# PinscapePico_KL25Z_Adapter_-_PCA9555_vsn.net
KiCad netlist of a schematic drawn in EAGLE
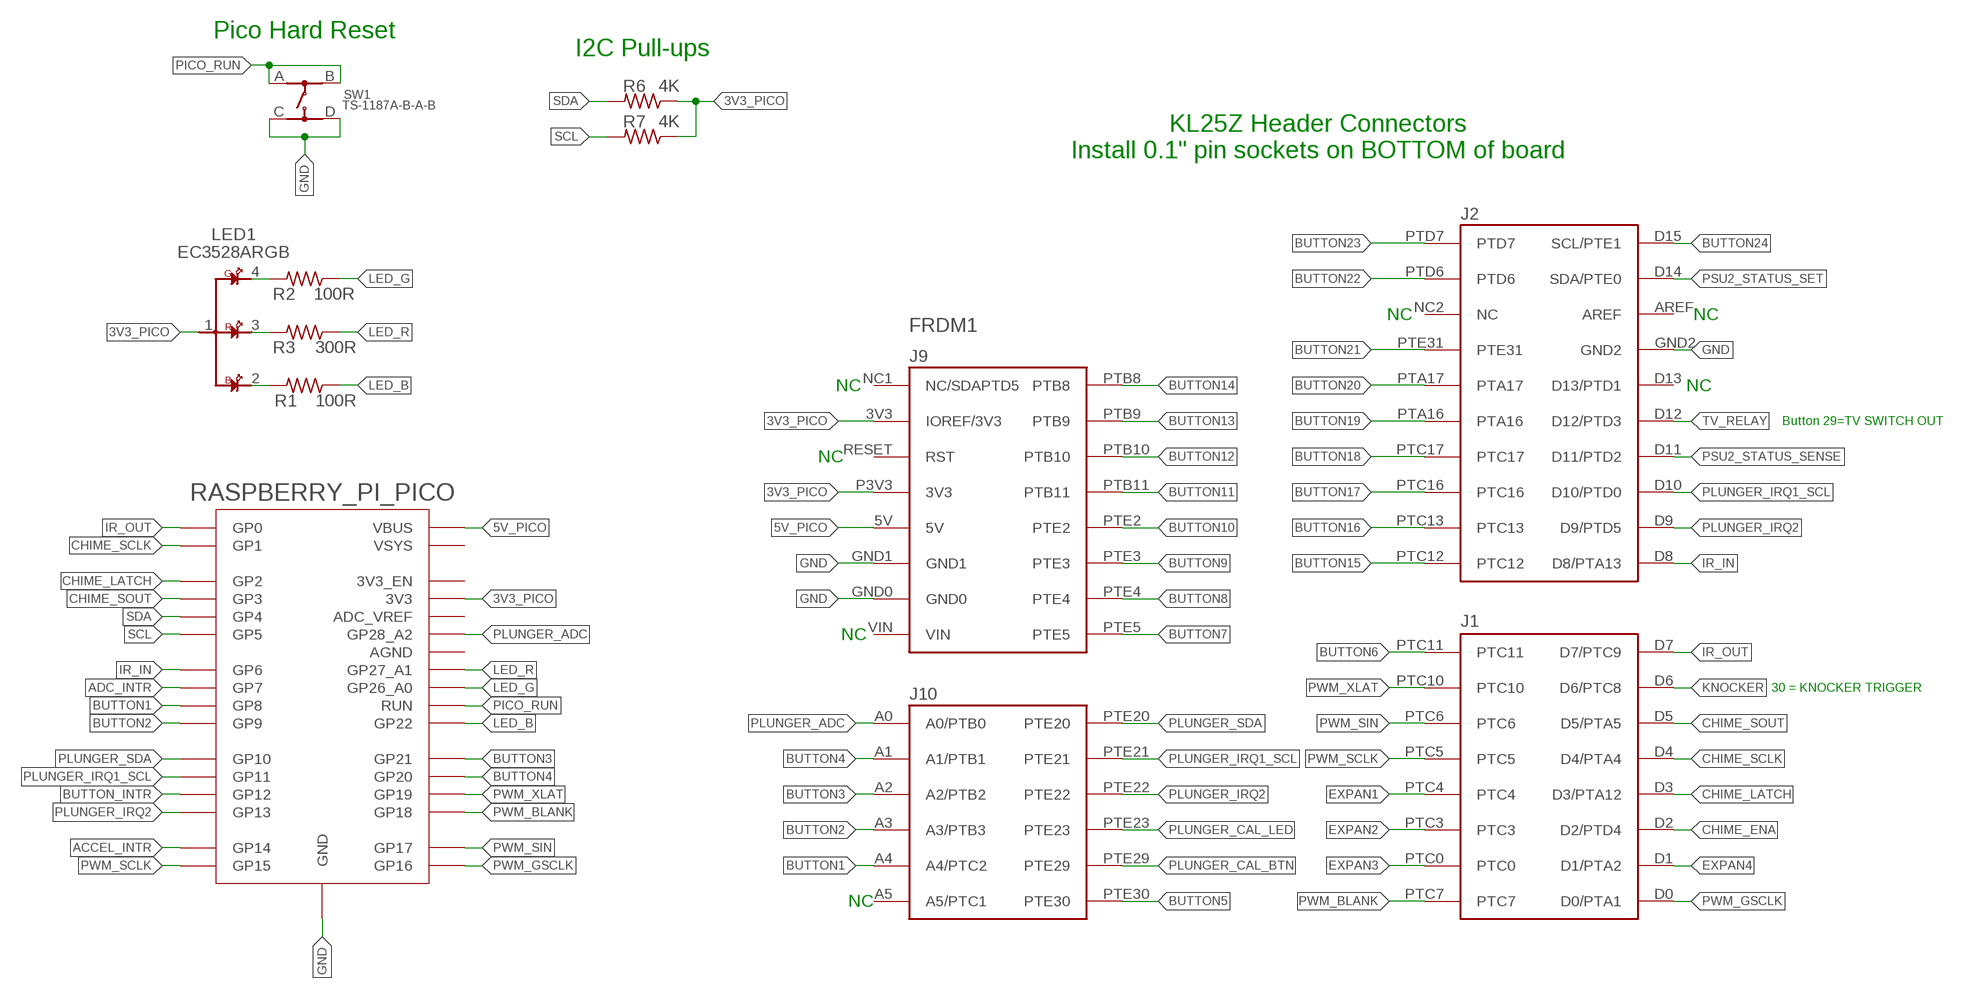
[diagram p0: schematic, sheet 1]
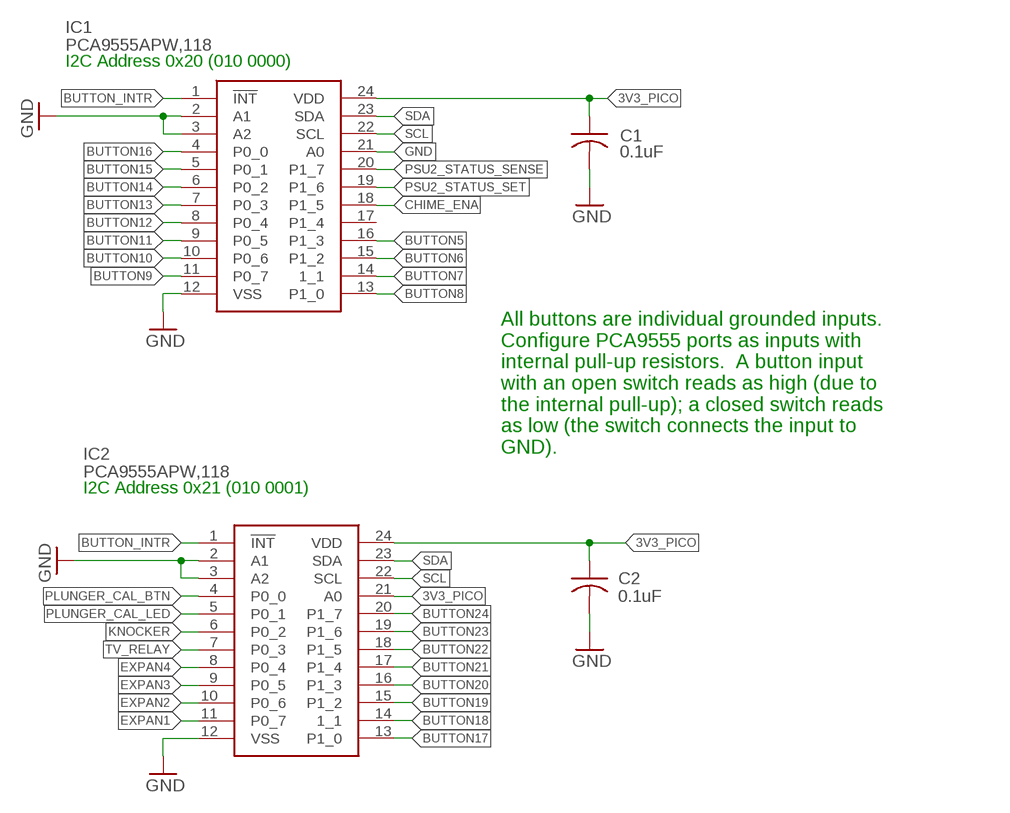
[diagram p1: schematic, sheet 2]
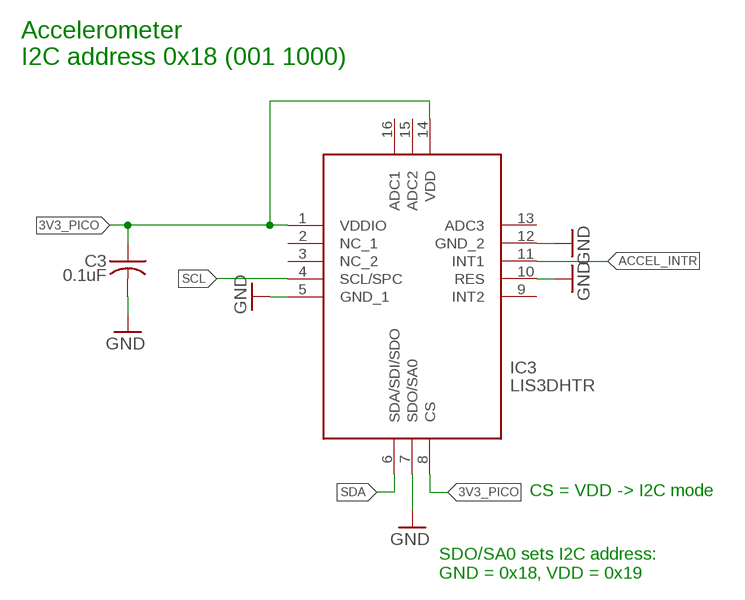
[diagram p2: schematic, sheet 3]
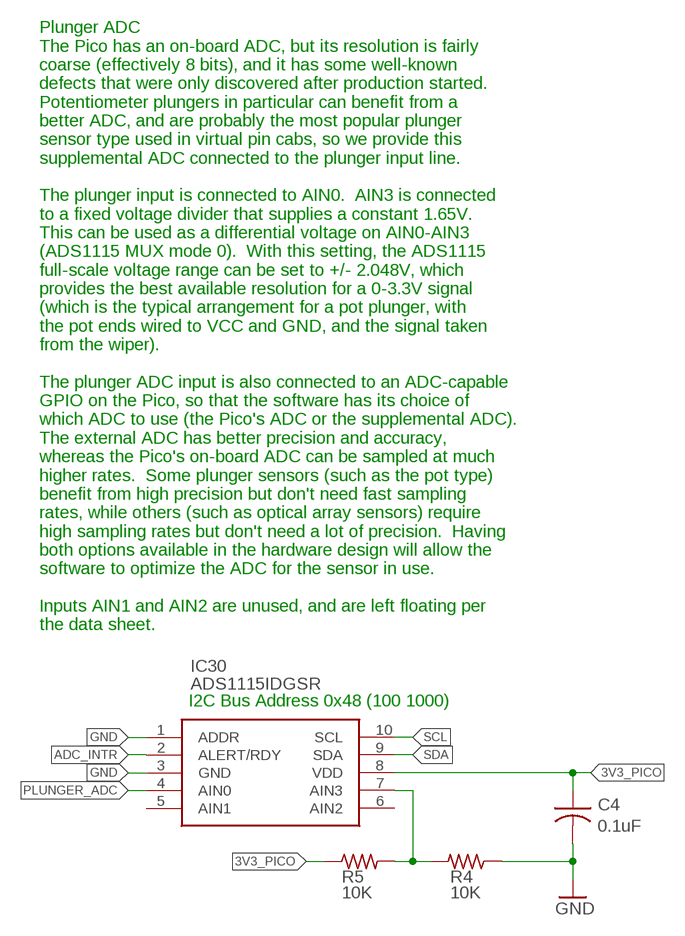
[diagram p3: schematic, sheet 4]

(export (version "E")
  (design (tool "Eeschema 10.0.6"))
  (components
    (comp (ref "C4")
      (value "0.1uF")
      (footprint "eagle-import:C1206")
      (libsource (lib "eagle-import") (part "C-USC1206"))
    )
    (comp (ref "IC30")
      (value "ADS1115IDGSR")
      (footprint "eagle-import:SOP50P490X110-10N")
      (fields (field (name "MOUSER_PART_NUMBER") "595-ADS1115IDGSR"))
      (libsource (lib "eagle-import") (part "ADS1115IDGSR"))
    )
    (comp (ref "R4")
      (value "10K")
      (footprint "eagle-import:R1206")
      (libsource (lib "eagle-import") (part "R-US_R1206"))
    )
    (comp (ref "R5")
      (value "10K")
      (footprint "eagle-import:R1206")
      (libsource (lib "eagle-import") (part "R-US_R1206"))
    )
    (comp (ref "C1")
      (value "0.1uF")
      (footprint "eagle-import:C1206")
      (libsource (lib "eagle-import") (part "C-USC1206"))
    )
    (comp (ref "C2")
      (value "0.1uF")
      (footprint "eagle-import:C1206")
      (libsource (lib "eagle-import") (part "C-USC1206"))
    )
    (comp (ref "IC1")
      (value "PCA9555APW,118")
      (footprint "eagle-import:SOP65P640X110-24N")
      (fields (field (name "MOUSER_PART_NUMBER") "771-PCA9555APW118"))
      (libsource (lib "eagle-import") (part "PCA9555APW,118"))
    )
    (comp (ref "IC2")
      (value "PCA9555APW,118")
      (footprint "eagle-import:SOP65P640X110-24N")
      (fields (field (name "MOUSER_PART_NUMBER") "771-PCA9555APW118"))
      (libsource (lib "eagle-import") (part "PCA9555APW,118"))
    )
    (comp (ref "FRDM1")
      (value "KL25Z")
      (footprint "eagle-import:FRDM_KL25Z_NORMAL")
      (libsource (lib "eagle-import") (part "FRDM-KL25ZNORMAL"))
    )
    (comp (ref "LED1")
      (value "EC3528ARGB")
      (footprint "eagle-import:EC3528ARGB")
      (libsource (lib "eagle-import") (part "EC3528ARGB"))
    )
    (comp (ref "R1")
      (value "100R")
      (footprint "eagle-import:R1206")
      (libsource (lib "eagle-import") (part "R-US_R1206"))
    )
    (comp (ref "R2")
      (value "100R")
      (footprint "eagle-import:R1206")
      (libsource (lib "eagle-import") (part "R-US_R1206"))
    )
    (comp (ref "R3")
      (value "300R")
      (footprint "eagle-import:R1206")
      (libsource (lib "eagle-import") (part "R-US_R1206"))
    )
    (comp (ref "R6")
      (value "4K")
      (footprint "eagle-import:R1206")
      (libsource (lib "eagle-import") (part "R-US_R1206"))
    )
    (comp (ref "R7")
      (value "4K")
      (footprint "eagle-import:R1206")
      (libsource (lib "eagle-import") (part "R-US_R1206"))
    )
    (comp (ref "RASPBERRY_PI_PICO")
      (value "RPI_PICO_NO_DEBUG")
      (footprint "eagle-import:RPI_PICO_TH_NO_DEBUG")
      (libsource (lib "eagle-import") (part "RPI_PICO_NO_DEBUG"))
    )
    (comp (ref "SW1")
      (value "TS-1187A-B-A-B")
      (footprint "eagle-import:TS-1187A-B-A-B")
      (libsource (lib "eagle-import") (part "TS-1187A-B-A-B"))
    )
    (comp (ref "C3")
      (value "0.1uF")
      (footprint "eagle-import:C1206")
      (libsource (lib "eagle-import") (part "C-USC1206"))
    )
    (comp (ref "IC3")
      (value "LIS3DHTR")
      (footprint "eagle-import:LIS3DHTR")
      (fields (field (name "MOUSER_PART_NUMBER") "511-LIS3DHTR"))
      (libsource (lib "eagle-import") (part "LIS3DHTR"))
    )
  )
  (nets
    (net (code "1") (name "3V3_PICO") (class "Default")
      (node (ref "C1") (pin "1") (pinfunction "1_1") (pintype "passive"))
      (node (ref "C2") (pin "1") (pinfunction "1_1") (pintype "passive"))
      (node (ref "C3") (pin "1") (pinfunction "1_1") (pintype "passive"))
      (node (ref "C4") (pin "1") (pinfunction "1_1") (pintype "passive"))
      (node (ref "FRDM1") (pin "3V3") (pinfunction "IOREF/3V3_3V3") (pintype "bidirectional"))
      (node (ref "FRDM1") (pin "P3V3") (pinfunction "3V3_P3V3") (pintype "bidirectional"))
      (node (ref "IC1") (pin "24") (pinfunction "VDD_24") (pintype "bidirectional"))
      (node (ref "IC2") (pin "21") (pinfunction "A0_21") (pintype "bidirectional"))
      (node (ref "IC2") (pin "24") (pinfunction "VDD_24") (pintype "bidirectional"))
      (node (ref "IC3") (pin "1") (pinfunction "VDDIO_1") (pintype "power_in"))
      (node (ref "IC3") (pin "14") (pinfunction "VDD_14") (pintype "power_in"))
      (node (ref "IC3") (pin "8") (pinfunction "CS_8") (pintype "input"))
      (node (ref "IC30") (pin "8") (pinfunction "VDD_8") (pintype "bidirectional"))
      (node (ref "LED1") (pin "1") (pinfunction "1_1") (pintype "bidirectional"))
      (node (ref "R5") (pin "1") (pinfunction "1_1") (pintype "passive"))
      (node (ref "R6") (pin "1") (pinfunction "1_1") (pintype "passive"))
      (node (ref "R7") (pin "1") (pinfunction "1_1") (pintype "passive"))
      (node (ref "RASPBERRY_PI_PICO") (pin "3V3") (pinfunction "3V3_3V3") (pintype "bidirectional"))
    )
    (net (code "2") (name "5V_PICO") (class "Default")
      (node (ref "FRDM1") (pin "5V") (pinfunction "5V_5V") (pintype "bidirectional"))
      (node (ref "RASPBERRY_PI_PICO") (pin "VBUS") (pinfunction "VBUS_VBUS") (pintype "bidirectional"))
    )
    (net (code "3") (name "ACCEL_INTR") (class "Default")
      (node (ref "IC3") (pin "11") (pinfunction "INT1_11") (pintype "input"))
      (node (ref "RASPBERRY_PI_PICO") (pin "GP14") (pinfunction "GP14_GP14") (pintype "bidirectional"))
    )
    (net (code "4") (name "ADC_INTR") (class "Default")
      (node (ref "IC30") (pin "2") (pinfunction "ALERT/RDY_2") (pintype "bidirectional"))
      (node (ref "RASPBERRY_PI_PICO") (pin "GP7") (pinfunction "GP7_GP7") (pintype "bidirectional"))
    )
    (net (code "5") (name "BUTTON1") (class "Default")
      (node (ref "FRDM1") (pin "A4") (pinfunction "A4/PTC2_A4") (pintype "bidirectional"))
      (node (ref "RASPBERRY_PI_PICO") (pin "GP8") (pinfunction "GP8_GP8") (pintype "bidirectional"))
    )
    (net (code "6") (name "BUTTON2") (class "Default")
      (node (ref "FRDM1") (pin "A3") (pinfunction "A3/PTB3_A3") (pintype "bidirectional"))
      (node (ref "RASPBERRY_PI_PICO") (pin "GP9") (pinfunction "GP9_GP9") (pintype "bidirectional"))
    )
    (net (code "7") (name "BUTTON3") (class "Default")
      (node (ref "FRDM1") (pin "A2") (pinfunction "A2/PTB2_A2") (pintype "bidirectional"))
      (node (ref "RASPBERRY_PI_PICO") (pin "GP21") (pinfunction "GP21_GP21") (pintype "bidirectional"))
    )
    (net (code "8") (name "BUTTON4") (class "Default")
      (node (ref "FRDM1") (pin "A1") (pinfunction "A1/PTB1_A1") (pintype "bidirectional"))
      (node (ref "RASPBERRY_PI_PICO") (pin "GP20") (pinfunction "GP20_GP20") (pintype "bidirectional"))
    )
    (net (code "9") (name "BUTTON5") (class "Default")
      (node (ref "FRDM1") (pin "PTE30") (pinfunction "PTE30_PTE30") (pintype "bidirectional"))
      (node (ref "IC1") (pin "16") (pinfunction "P1_3_16") (pintype "bidirectional"))
    )
    (net (code "10") (name "BUTTON6") (class "Default")
      (node (ref "FRDM1") (pin "PTC11") (pinfunction "PTC11_PTC11") (pintype "bidirectional"))
      (node (ref "IC1") (pin "15") (pinfunction "P1_2_15") (pintype "bidirectional"))
    )
    (net (code "11") (name "BUTTON7") (class "Default")
      (node (ref "FRDM1") (pin "PTE5") (pinfunction "PTE5_PTE5") (pintype "bidirectional"))
      (node (ref "IC1") (pin "14") (pinfunction "1_1_14") (pintype "bidirectional"))
    )
    (net (code "12") (name "BUTTON8") (class "Default")
      (node (ref "FRDM1") (pin "PTE4") (pinfunction "PTE4_PTE4") (pintype "bidirectional"))
      (node (ref "IC1") (pin "13") (pinfunction "P1_0_13") (pintype "bidirectional"))
    )
    (net (code "13") (name "BUTTON9") (class "Default")
      (node (ref "FRDM1") (pin "PTE3") (pinfunction "PTE3_PTE3") (pintype "bidirectional"))
      (node (ref "IC1") (pin "11") (pinfunction "P0_7_11") (pintype "bidirectional"))
    )
    (net (code "14") (name "BUTTON10") (class "Default")
      (node (ref "FRDM1") (pin "PTE2") (pinfunction "PTE2_PTE2") (pintype "bidirectional"))
      (node (ref "IC1") (pin "10") (pinfunction "P0_6_10") (pintype "bidirectional"))
    )
    (net (code "15") (name "BUTTON11") (class "Default")
      (node (ref "FRDM1") (pin "PTB11") (pinfunction "PTB11_PTB11") (pintype "bidirectional"))
      (node (ref "IC1") (pin "9") (pinfunction "P0_5_9") (pintype "bidirectional"))
    )
    (net (code "16") (name "BUTTON12") (class "Default")
      (node (ref "FRDM1") (pin "PTB10") (pinfunction "PTB10_PTB10") (pintype "bidirectional"))
      (node (ref "IC1") (pin "8") (pinfunction "P0_4_8") (pintype "bidirectional"))
    )
    (net (code "17") (name "BUTTON13") (class "Default")
      (node (ref "FRDM1") (pin "PTB9") (pinfunction "PTB9_PTB9") (pintype "bidirectional"))
      (node (ref "IC1") (pin "7") (pinfunction "P0_3_7") (pintype "bidirectional"))
    )
    (net (code "18") (name "BUTTON14") (class "Default")
      (node (ref "FRDM1") (pin "PTB8") (pinfunction "PTB8_PTB8") (pintype "bidirectional"))
      (node (ref "IC1") (pin "6") (pinfunction "P0_2_6") (pintype "bidirectional"))
    )
    (net (code "19") (name "BUTTON15") (class "Default")
      (node (ref "FRDM1") (pin "PTC12") (pinfunction "PTC12_PTC12") (pintype "bidirectional"))
      (node (ref "IC1") (pin "5") (pinfunction "P0_1_5") (pintype "bidirectional"))
    )
    (net (code "20") (name "BUTTON16") (class "Default")
      (node (ref "FRDM1") (pin "PTC13") (pinfunction "PTC13_PTC13") (pintype "bidirectional"))
      (node (ref "IC1") (pin "4") (pinfunction "P0_0_4") (pintype "bidirectional"))
    )
    (net (code "21") (name "BUTTON17") (class "Default")
      (node (ref "FRDM1") (pin "PTC16") (pinfunction "PTC16_PTC16") (pintype "bidirectional"))
      (node (ref "IC2") (pin "13") (pinfunction "P1_0_13") (pintype "bidirectional"))
    )
    (net (code "22") (name "BUTTON18") (class "Default")
      (node (ref "FRDM1") (pin "PTC17") (pinfunction "PTC17_PTC17") (pintype "bidirectional"))
      (node (ref "IC2") (pin "14") (pinfunction "1_1_14") (pintype "bidirectional"))
    )
    (net (code "23") (name "BUTTON19") (class "Default")
      (node (ref "FRDM1") (pin "PTA16") (pinfunction "PTA16_PTA16") (pintype "bidirectional"))
      (node (ref "IC2") (pin "15") (pinfunction "P1_2_15") (pintype "bidirectional"))
    )
    (net (code "24") (name "BUTTON20") (class "Default")
      (node (ref "FRDM1") (pin "PTA17") (pinfunction "PTA17_PTA17") (pintype "bidirectional"))
      (node (ref "IC2") (pin "16") (pinfunction "P1_3_16") (pintype "bidirectional"))
    )
    (net (code "25") (name "BUTTON21") (class "Default")
      (node (ref "FRDM1") (pin "PTE31") (pinfunction "PTE31_PTE31") (pintype "bidirectional"))
      (node (ref "IC2") (pin "17") (pinfunction "P1_4_17") (pintype "bidirectional"))
    )
    (net (code "26") (name "BUTTON22") (class "Default")
      (node (ref "FRDM1") (pin "PTD6") (pinfunction "PTD6_PTD6") (pintype "bidirectional"))
      (node (ref "IC2") (pin "18") (pinfunction "P1_5_18") (pintype "bidirectional"))
    )
    (net (code "27") (name "BUTTON23") (class "Default")
      (node (ref "FRDM1") (pin "PTD7") (pinfunction "PTD7_PTD7") (pintype "bidirectional"))
      (node (ref "IC2") (pin "19") (pinfunction "P1_6_19") (pintype "bidirectional"))
    )
    (net (code "28") (name "BUTTON24") (class "Default")
      (node (ref "FRDM1") (pin "D15") (pinfunction "SCL/PTE1_D15") (pintype "bidirectional"))
      (node (ref "IC2") (pin "20") (pinfunction "P1_7_20") (pintype "bidirectional"))
    )
    (net (code "29") (name "BUTTON_INTR") (class "Default")
      (node (ref "IC1") (pin "1") (pinfunction "~{INT}_1") (pintype "bidirectional"))
      (node (ref "IC2") (pin "1") (pinfunction "~{INT}_1") (pintype "bidirectional"))
      (node (ref "RASPBERRY_PI_PICO") (pin "GP12") (pinfunction "GP12_GP12") (pintype "bidirectional"))
    )
    (net (code "30") (name "CHIME_ENA") (class "Default")
      (node (ref "FRDM1") (pin "D2") (pinfunction "D2/PTD4_D2") (pintype "bidirectional"))
      (node (ref "IC1") (pin "18") (pinfunction "P1_5_18") (pintype "bidirectional"))
    )
    (net (code "31") (name "CHIME_LATCH") (class "Default")
      (node (ref "FRDM1") (pin "D3") (pinfunction "D3/PTA12_D3") (pintype "bidirectional"))
      (node (ref "RASPBERRY_PI_PICO") (pin "GP2") (pinfunction "GP2_GP2") (pintype "bidirectional"))
    )
    (net (code "32") (name "CHIME_SCLK") (class "Default")
      (node (ref "FRDM1") (pin "D4") (pinfunction "D4/PTA4_D4") (pintype "bidirectional"))
      (node (ref "RASPBERRY_PI_PICO") (pin "GP1") (pinfunction "GP1_GP1") (pintype "bidirectional"))
    )
    (net (code "33") (name "CHIME_SOUT") (class "Default")
      (node (ref "FRDM1") (pin "D5") (pinfunction "D5/PTA5_D5") (pintype "bidirectional"))
      (node (ref "RASPBERRY_PI_PICO") (pin "GP3") (pinfunction "GP3_GP3") (pintype "bidirectional"))
    )
    (net (code "34") (name "EXPAN1") (class "Default")
      (node (ref "FRDM1") (pin "PTC4") (pinfunction "PTC4_PTC4") (pintype "bidirectional"))
      (node (ref "IC2") (pin "11") (pinfunction "P0_7_11") (pintype "bidirectional"))
    )
    (net (code "35") (name "EXPAN2") (class "Default")
      (node (ref "FRDM1") (pin "PTC3") (pinfunction "PTC3_PTC3") (pintype "bidirectional"))
      (node (ref "IC2") (pin "10") (pinfunction "P0_6_10") (pintype "bidirectional"))
    )
    (net (code "36") (name "EXPAN3") (class "Default")
      (node (ref "FRDM1") (pin "PTC0") (pinfunction "PTC0_PTC0") (pintype "bidirectional"))
      (node (ref "IC2") (pin "9") (pinfunction "P0_5_9") (pintype "bidirectional"))
    )
    (net (code "37") (name "EXPAN4") (class "Default")
      (node (ref "FRDM1") (pin "D1") (pinfunction "D1/PTA2_D1") (pintype "bidirectional"))
      (node (ref "IC2") (pin "8") (pinfunction "P0_4_8") (pintype "bidirectional"))
    )
    (net (code "38") (name "GND") (class "Default")
      (node (ref "C1") (pin "2") (pinfunction "2_2") (pintype "passive"))
      (node (ref "C2") (pin "2") (pinfunction "2_2") (pintype "passive"))
      (node (ref "C3") (pin "2") (pinfunction "2_2") (pintype "passive"))
      (node (ref "C4") (pin "2") (pinfunction "2_2") (pintype "passive"))
      (node (ref "FRDM1") (pin "GND0") (pinfunction "GND0_GND0") (pintype "bidirectional"))
      (node (ref "FRDM1") (pin "GND1") (pinfunction "GND1_GND1") (pintype "bidirectional"))
      (node (ref "FRDM1") (pin "GND2") (pinfunction "GND2_GND2") (pintype "bidirectional"))
      (node (ref "IC1") (pin "12") (pinfunction "VSS_12") (pintype "bidirectional"))
      (node (ref "IC1") (pin "2") (pinfunction "A1_2") (pintype "bidirectional"))
      (node (ref "IC1") (pin "21") (pinfunction "A0_21") (pintype "bidirectional"))
      (node (ref "IC1") (pin "3") (pinfunction "A2_3") (pintype "bidirectional"))
      (node (ref "IC2") (pin "12") (pinfunction "VSS_12") (pintype "bidirectional"))
      (node (ref "IC2") (pin "2") (pinfunction "A1_2") (pintype "bidirectional"))
      (node (ref "IC2") (pin "3") (pinfunction "A2_3") (pintype "bidirectional"))
      (node (ref "IC3") (pin "10") (pinfunction "RES_10") (pintype "bidirectional"))
      (node (ref "IC3") (pin "12") (pinfunction "GND_2_12") (pintype "power_in"))
      (node (ref "IC3") (pin "5") (pinfunction "GND_1_5") (pintype "power_in"))
      (node (ref "IC3") (pin "7") (pinfunction "SDO/SA0_7") (pintype "bidirectional"))
      (node (ref "IC30") (pin "1") (pinfunction "ADDR_1") (pintype "bidirectional"))
      (node (ref "IC30") (pin "3") (pinfunction "GND_3") (pintype "bidirectional"))
      (node (ref "R4") (pin "1") (pinfunction "1_1") (pintype "passive"))
      (node (ref "RASPBERRY_PI_PICO") (pin "GND@1") (pinfunction "GND_GND@1") (pintype "bidirectional"))
      (node (ref "RASPBERRY_PI_PICO") (pin "GND@2") (pinfunction "GND_GND@2") (pintype "bidirectional"))
      (node (ref "RASPBERRY_PI_PICO") (pin "GND@3") (pinfunction "GND_GND@3") (pintype "bidirectional"))
      (node (ref "RASPBERRY_PI_PICO") (pin "GND@4") (pinfunction "GND_GND@4") (pintype "bidirectional"))
      (node (ref "RASPBERRY_PI_PICO") (pin "GND@6") (pinfunction "GND_GND@6") (pintype "bidirectional"))
      (node (ref "RASPBERRY_PI_PICO") (pin "GND@7") (pinfunction "GND_GND@7") (pintype "bidirectional"))
      (node (ref "RASPBERRY_PI_PICO") (pin "GND@8") (pinfunction "GND_GND@8") (pintype "bidirectional"))
      (node (ref "SW1") (pin "C") (pinfunction "C_C") (pintype "bidirectional"))
      (node (ref "SW1") (pin "D") (pinfunction "D_D") (pintype "bidirectional"))
    )
    (net (code "39") (name "IR_IN") (class "Default")
      (node (ref "FRDM1") (pin "D8") (pinfunction "D8/PTA13_D8") (pintype "bidirectional"))
      (node (ref "RASPBERRY_PI_PICO") (pin "GP6") (pinfunction "GP6_GP6") (pintype "bidirectional"))
    )
    (net (code "40") (name "IR_OUT") (class "Default")
      (node (ref "FRDM1") (pin "D7") (pinfunction "D7/PTC9_D7") (pintype "bidirectional"))
      (node (ref "RASPBERRY_PI_PICO") (pin "GP0") (pinfunction "GP0_GP0") (pintype "bidirectional"))
    )
    (net (code "41") (name "KNOCKER") (class "Default")
      (node (ref "FRDM1") (pin "D6") (pinfunction "D6/PTC8_D6") (pintype "bidirectional"))
      (node (ref "IC2") (pin "6") (pinfunction "P0_2_6") (pintype "bidirectional"))
    )
    (net (code "42") (name "LED_B") (class "Default")
      (node (ref "R1") (pin "1") (pinfunction "1_1") (pintype "passive"))
      (node (ref "RASPBERRY_PI_PICO") (pin "GP22") (pinfunction "GP22_GP22") (pintype "bidirectional"))
    )
    (net (code "43") (name "LED_G") (class "Default")
      (node (ref "R2") (pin "1") (pinfunction "1_1") (pintype "passive"))
      (node (ref "RASPBERRY_PI_PICO") (pin "GP26_A0") (pinfunction "GP26_A0_GP26_A0") (pintype "bidirectional"))
    )
    (net (code "44") (name "LED_R") (class "Default")
      (node (ref "R3") (pin "1") (pinfunction "1_1") (pintype "passive"))
      (node (ref "RASPBERRY_PI_PICO") (pin "GP27_A1") (pinfunction "GP27_A1_GP27_A1") (pintype "bidirectional"))
    )
    (net (code "45") (name "Net-(IC30-AIN3)") (class "Default")
      (node (ref "IC30") (pin "7") (pinfunction "AIN3_7") (pintype "bidirectional"))
      (node (ref "R4") (pin "2") (pinfunction "2_2") (pintype "passive"))
      (node (ref "R5") (pin "2") (pinfunction "2_2") (pintype "passive"))
    )
    (net (code "46") (name "Net-(LED1-Pad2)") (class "Default")
      (node (ref "LED1") (pin "2") (pinfunction "2_2") (pintype "bidirectional"))
      (node (ref "R1") (pin "2") (pinfunction "2_2") (pintype "passive"))
    )
    (net (code "47") (name "Net-(LED1-Pad3)") (class "Default")
      (node (ref "LED1") (pin "3") (pinfunction "3_3") (pintype "bidirectional"))
      (node (ref "R3") (pin "2") (pinfunction "2_2") (pintype "passive"))
    )
    (net (code "48") (name "Net-(LED1-Pad4)") (class "Default")
      (node (ref "LED1") (pin "4") (pinfunction "4_4") (pintype "bidirectional"))
      (node (ref "R2") (pin "2") (pinfunction "2_2") (pintype "passive"))
    )
    (net (code "49") (name "PICO_RUN") (class "Default")
      (node (ref "RASPBERRY_PI_PICO") (pin "RUN") (pinfunction "RUN_RUN") (pintype "bidirectional"))
      (node (ref "SW1") (pin "A") (pinfunction "A_A") (pintype "bidirectional"))
      (node (ref "SW1") (pin "B") (pinfunction "B_B") (pintype "bidirectional"))
    )
    (net (code "50") (name "PLUNGER_ADC") (class "Default")
      (node (ref "FRDM1") (pin "A0") (pinfunction "A0/PTB0_A0") (pintype "bidirectional"))
      (node (ref "IC30") (pin "4") (pinfunction "AIN0_4") (pintype "bidirectional"))
      (node (ref "RASPBERRY_PI_PICO") (pin "GP28_A2") (pinfunction "GP28_A2_GP28_A2") (pintype "bidirectional"))
    )
    (net (code "51") (name "PLUNGER_CAL_BTN") (class "Default")
      (node (ref "FRDM1") (pin "PTE29") (pinfunction "PTE29_PTE29") (pintype "bidirectional"))
      (node (ref "IC2") (pin "4") (pinfunction "P0_0_4") (pintype "bidirectional"))
    )
    (net (code "52") (name "PLUNGER_CAL_LED") (class "Default")
      (node (ref "FRDM1") (pin "PTE23") (pinfunction "PTE23_PTE23") (pintype "bidirectional"))
      (node (ref "IC2") (pin "5") (pinfunction "P0_1_5") (pintype "bidirectional"))
    )
    (net (code "53") (name "PLUNGER_IRQ1_SCL") (class "Default")
      (node (ref "FRDM1") (pin "D10") (pinfunction "D10/PTD0_D10") (pintype "bidirectional"))
      (node (ref "FRDM1") (pin "PTE21") (pinfunction "PTE21_PTE21") (pintype "bidirectional"))
      (node (ref "RASPBERRY_PI_PICO") (pin "GP11") (pinfunction "GP11_GP11") (pintype "bidirectional"))
    )
    (net (code "54") (name "PLUNGER_IRQ2") (class "Default")
      (node (ref "FRDM1") (pin "D9") (pinfunction "D9/PTD5_D9") (pintype "bidirectional"))
      (node (ref "FRDM1") (pin "PTE22") (pinfunction "PTE22_PTE22") (pintype "bidirectional"))
      (node (ref "RASPBERRY_PI_PICO") (pin "GP13") (pinfunction "GP13_GP13") (pintype "bidirectional"))
    )
    (net (code "55") (name "PLUNGER_SDA") (class "Default")
      (node (ref "FRDM1") (pin "PTE20") (pinfunction "PTE20_PTE20") (pintype "bidirectional"))
      (node (ref "RASPBERRY_PI_PICO") (pin "GP10") (pinfunction "GP10_GP10") (pintype "bidirectional"))
    )
    (net (code "56") (name "PSU2_STATUS_SENSE") (class "Default")
      (node (ref "FRDM1") (pin "D11") (pinfunction "D11/PTD2_D11") (pintype "bidirectional"))
      (node (ref "IC1") (pin "20") (pinfunction "P1_7_20") (pintype "bidirectional"))
    )
    (net (code "57") (name "PSU2_STATUS_SET") (class "Default")
      (node (ref "FRDM1") (pin "D14") (pinfunction "SDA/PTE0_D14") (pintype "bidirectional"))
      (node (ref "IC1") (pin "19") (pinfunction "P1_6_19") (pintype "bidirectional"))
    )
    (net (code "58") (name "PWM_BLANK") (class "Default")
      (node (ref "FRDM1") (pin "PTC7") (pinfunction "PTC7_PTC7") (pintype "bidirectional"))
      (node (ref "RASPBERRY_PI_PICO") (pin "GP18") (pinfunction "GP18_GP18") (pintype "bidirectional"))
    )
    (net (code "59") (name "PWM_GSCLK") (class "Default")
      (node (ref "FRDM1") (pin "D0") (pinfunction "D0/PTA1_D0") (pintype "bidirectional"))
      (node (ref "RASPBERRY_PI_PICO") (pin "GP16") (pinfunction "GP16_GP16") (pintype "bidirectional"))
    )
    (net (code "60") (name "PWM_SCLK") (class "Default")
      (node (ref "FRDM1") (pin "PTC5") (pinfunction "PTC5_PTC5") (pintype "bidirectional"))
      (node (ref "RASPBERRY_PI_PICO") (pin "GP15") (pinfunction "GP15_GP15") (pintype "bidirectional"))
    )
    (net (code "61") (name "PWM_SIN") (class "Default")
      (node (ref "FRDM1") (pin "PTC6") (pinfunction "PTC6_PTC6") (pintype "bidirectional"))
      (node (ref "RASPBERRY_PI_PICO") (pin "GP17") (pinfunction "GP17_GP17") (pintype "bidirectional"))
    )
    (net (code "62") (name "PWM_XLAT") (class "Default")
      (node (ref "FRDM1") (pin "PTC10") (pinfunction "PTC10_PTC10") (pintype "bidirectional"))
      (node (ref "RASPBERRY_PI_PICO") (pin "GP19") (pinfunction "GP19_GP19") (pintype "bidirectional"))
    )
    (net (code "63") (name "SCL") (class "Default")
      (node (ref "IC1") (pin "22") (pinfunction "SCL_22") (pintype "bidirectional"))
      (node (ref "IC2") (pin "22") (pinfunction "SCL_22") (pintype "bidirectional"))
      (node (ref "IC3") (pin "4") (pinfunction "SCL/SPC_4") (pintype "bidirectional"))
      (node (ref "IC30") (pin "10") (pinfunction "SCL_10") (pintype "bidirectional"))
      (node (ref "R7") (pin "2") (pinfunction "2_2") (pintype "passive"))
      (node (ref "RASPBERRY_PI_PICO") (pin "GP5") (pinfunction "GP5_GP5") (pintype "bidirectional"))
    )
    (net (code "64") (name "SDA") (class "Default")
      (node (ref "IC1") (pin "23") (pinfunction "SDA_23") (pintype "bidirectional"))
      (node (ref "IC2") (pin "23") (pinfunction "SDA_23") (pintype "bidirectional"))
      (node (ref "IC3") (pin "6") (pinfunction "SDA/SDI/SDO_6") (pintype "bidirectional"))
      (node (ref "IC30") (pin "9") (pinfunction "SDA_9") (pintype "bidirectional"))
      (node (ref "R6") (pin "2") (pinfunction "2_2") (pintype "passive"))
      (node (ref "RASPBERRY_PI_PICO") (pin "GP4") (pinfunction "GP4_GP4") (pintype "bidirectional"))
    )
    (net (code "65") (name "TV_RELAY") (class "Default")
      (node (ref "FRDM1") (pin "D12") (pinfunction "D12/PTD3_D12") (pintype "bidirectional"))
      (node (ref "IC2") (pin "7") (pinfunction "P0_3_7") (pintype "bidirectional"))
    )
    (net (code "66") (name "unconnected-(FRDM1-A5{slash}PTC1-PadA5)") (class "Default")
      (node (ref "FRDM1") (pin "A5") (pinfunction "A5/PTC1_A5") (pintype "bidirectional"))
    )
    (net (code "67") (name "unconnected-(FRDM1-D13{slash}PTD1-PadD13)") (class "Default")
      (node (ref "FRDM1") (pin "D13") (pinfunction "D13/PTD1_D13") (pintype "bidirectional"))
    )
    (net (code "68") (name "unconnected-(FRDM1-NC-PadNC2)") (class "Default")
      (node (ref "FRDM1") (pin "NC2") (pinfunction "NC_NC2") (pintype "bidirectional"))
    )
    (net (code "69") (name "unconnected-(FRDM1-NC{slash}SDAPTD5-PadNC1)") (class "Default")
      (node (ref "FRDM1") (pin "NC1") (pinfunction "NC/SDAPTD5_NC1") (pintype "bidirectional"))
    )
    (net (code "70") (name "unconnected-(FRDM1-PadAREF)") (class "Default")
      (node (ref "FRDM1") (pin "AREF") (pinfunction "AREF_AREF") (pintype "bidirectional"))
    )
    (net (code "71") (name "unconnected-(FRDM1-PadVIN)") (class "Default")
      (node (ref "FRDM1") (pin "VIN") (pinfunction "VIN_VIN") (pintype "bidirectional"))
    )
    (net (code "72") (name "unconnected-(FRDM1-RST-PadRESET)") (class "Default")
      (node (ref "FRDM1") (pin "RESET") (pinfunction "RST_RESET") (pintype "bidirectional"))
    )
    (net (code "73") (name "unconnected-(IC1-P1_4-Pad17)") (class "Default")
      (node (ref "IC1") (pin "17") (pinfunction "P1_4_17") (pintype "bidirectional"))
    )
    (net (code "74") (name "unconnected-(IC3-ADC1-Pad16)") (class "Default")
      (node (ref "IC3") (pin "16") (pinfunction "ADC1_16") (pintype "bidirectional"))
    )
    (net (code "75") (name "unconnected-(IC3-ADC2-Pad15)") (class "Default")
      (node (ref "IC3") (pin "15") (pinfunction "ADC2_15") (pintype "bidirectional"))
    )
    (net (code "76") (name "unconnected-(IC3-ADC3-Pad13)") (class "Default")
      (node (ref "IC3") (pin "13") (pinfunction "ADC3_13") (pintype "bidirectional"))
    )
    (net (code "77") (name "unconnected-(IC3-INT2-Pad9)") (class "Default")
      (node (ref "IC3") (pin "9") (pinfunction "INT2_9") (pintype "input"))
    )
    (net (code "78") (name "unconnected-(IC3-NC_1-Pad2)") (class "Default")
      (node (ref "IC3") (pin "2") (pinfunction "NC_1_2") (pintype "bidirectional"))
    )
    (net (code "79") (name "unconnected-(IC3-NC_2-Pad3)") (class "Default")
      (node (ref "IC3") (pin "3") (pinfunction "NC_2_3") (pintype "bidirectional"))
    )
    (net (code "80") (name "unconnected-(IC30-AIN1-Pad5)") (class "Default")
      (node (ref "IC30") (pin "5") (pinfunction "AIN1_5") (pintype "bidirectional"))
    )
    (net (code "81") (name "unconnected-(IC30-AIN2-Pad6)") (class "Default")
      (node (ref "IC30") (pin "6") (pinfunction "AIN2_6") (pintype "bidirectional"))
    )
    (net (code "82") (name "unconnected-(RASPBERRY_PI_PICO-Pad3V3_EN)") (class "Default")
      (node (ref "RASPBERRY_PI_PICO") (pin "3V3_EN") (pinfunction "3V3_EN_3V3_EN") (pintype "bidirectional"))
    )
    (net (code "83") (name "unconnected-(RASPBERRY_PI_PICO-PadADC_VREF)") (class "Default")
      (node (ref "RASPBERRY_PI_PICO") (pin "ADC_VREF") (pinfunction "ADC_VREF_ADC_VREF") (pintype "bidirectional"))
    )
    (net (code "84") (name "unconnected-(RASPBERRY_PI_PICO-PadAGND)") (class "Default")
      (node (ref "RASPBERRY_PI_PICO") (pin "AGND") (pinfunction "AGND_AGND") (pintype "bidirectional"))
    )
    (net (code "85") (name "unconnected-(RASPBERRY_PI_PICO-PadVSYS)") (class "Default")
      (node (ref "RASPBERRY_PI_PICO") (pin "VSYS") (pinfunction "VSYS_VSYS") (pintype "bidirectional"))
    )
  )
)
